# SR_latch.net
KiCad netlist of a schematic drawn in Altium Designer
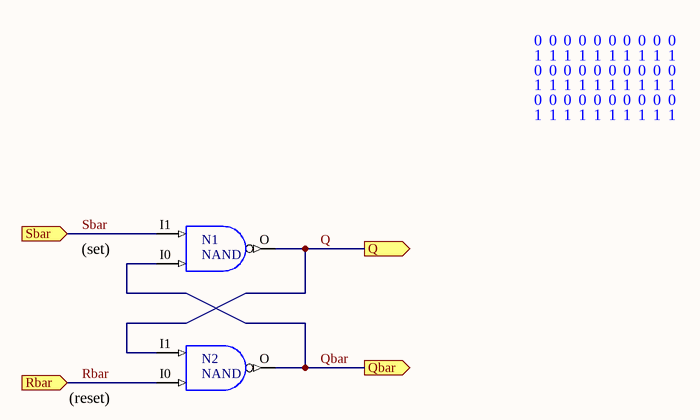
[diagram p0: SR_latch.SchDoc]

(export (version "E")
  (design (tool "Eeschema 10.0.6"))
  (components
    (comp (ref "N1")
      (value "NAND")
      (description "2-Input NAND Gate")
      (fields (field (name "PUBLISHER") "Altium Limited"))
      (libsource (lib "CUPL PLD Programming") (part "NAND2"))
    )
    (comp (ref "N2")
      (value "NAND")
      (description "2-Input NAND Gate")
      (fields (field (name "PUBLISHER") "Altium Limited"))
      (libsource (lib "CUPL PLD Programming") (part "NAND2"))
    )
  )
  (nets
    (net (code "1") (name "/Q") (class "Default")
      (node (ref "N1") (pin "O") (pinfunction "O_O") (pintype "output"))
      (node (ref "N2") (pin "I1") (pinfunction "I1_I1") (pintype "input"))
    )
    (net (code "2") (name "/Qbar") (class "Default")
      (node (ref "N1") (pin "I0") (pinfunction "I0_I0") (pintype "input"))
      (node (ref "N2") (pin "O") (pinfunction "O_O") (pintype "output"))
    )
    (net (code "3") (name "/Rbar") (class "Default")
      (node (ref "N2") (pin "I0") (pinfunction "I0_I0") (pintype "input"))
    )
    (net (code "4") (name "/Sbar") (class "Default")
      (node (ref "N1") (pin "I1") (pinfunction "I1_I1") (pintype "input"))
    )
  )
)
